# 02-M2_GoldFingers.net
KiCad netlist of a schematic drawn in Altium Designer
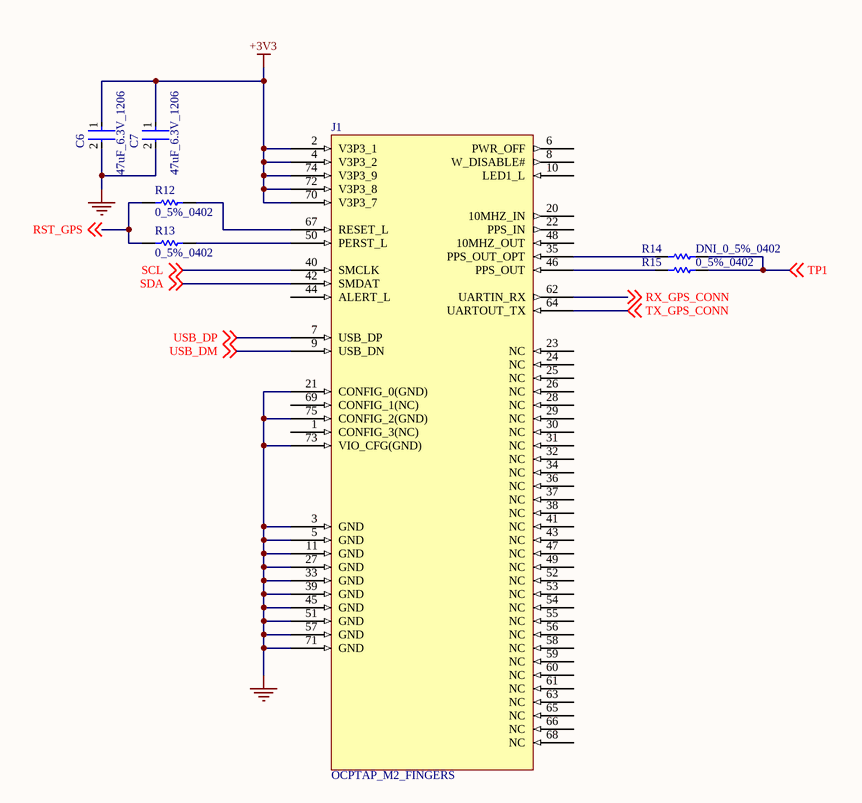
[diagram p0: 02-M2_GoldFingers.SchDoc]

(export (version "E")
  (design (tool "Eeschema 10.0.6"))
  (components
    (comp (ref "C6")
      (value "47uF_6.3V_1206")
      (footprint "FP-GRM31C-0_2-e0_3_0_8-IPC_C")
      (description "Chip Multilayer Ceramic Capacitors for General Purpose, 1206, 47uF, X5R, 15%, 20%, 6.3V")
      (fields (field (name "TOLERANCE") "20%") (field (name "VOLTAGE") "6.3V"))
      (libsource (lib "Altium Content Vault") (part "02cd4be3c70576c341d710602a673aa"))
    )
    (comp (ref "C7")
      (value "47uF_6.3V_1206")
      (footprint "FP-GRM31C-0_2-e0_3_0_8-IPC_C")
      (description "Chip Multilayer Ceramic Capacitors for General Purpose, 1206, 47uF, X5R, 15%, 20%, 6.3V")
      (fields (field (name "TOLERANCE") "20%") (field (name "VOLTAGE") "6.3V"))
      (libsource (lib "Altium Content Vault") (part "02cd4be3c70576c341d710602a673aa"))
    )
    (comp (ref "J1")
      (value "OCPTAP_M2_FINGERS")
      (footprint "OCPTAP M2 FINGERS")
      (libsource (lib "M2_Library") (part "OCPTAP_M2_FINGERS"))
    )
    (comp (ref "R12")
      (value "0_5%_0402")
      (footprint "RESC1005X40X25NL05T10")
      (fields (field (name "MANUFACTURER") "Panasonic") (field (name "PART NUMBER") "ERJ-U020R00X"))
      (libsource (lib "Altium Content Vault") (part "RES"))
    )
    (comp (ref "R13")
      (value "0_5%_0402")
      (footprint "RESC1005X40X25NL05T10")
      (fields (field (name "MANUFACTURER") "Panasonic") (field (name "PART NUMBER") "ERJ-U020R00X"))
      (libsource (lib "Altium Content Vault") (part "RES"))
    )
    (comp (ref "R14")
      (value "DNI_0_5%_0402")
      (footprint "RESC1005X40X25NL05T10")
      (fields (field (name "MANUFACTURER") "Panasonic") (field (name "PART NUMBER") "ERJ-U020R00X"))
      (libsource (lib "Altium Content Vault") (part "RES"))
    )
    (comp (ref "R15")
      (value "0_5%_0402")
      (footprint "RESC1005X40X25NL05T10")
      (fields (field (name "MANUFACTURER") "Panasonic") (field (name "PART NUMBER") "ERJ-U020R00X"))
      (libsource (lib "Altium Content Vault") (part "RES"))
    )
  )
  (nets
    (net (code "1") (name "+3V3") (class "Default")
      (node (ref "C6") (pin "1") (pinfunction "1_1") (pintype "passive"))
      (node (ref "C7") (pin "1") (pinfunction "1_1") (pintype "passive"))
      (node (ref "J1") (pin "2") (pinfunction "V3P3_1_2") (pintype "input"))
      (node (ref "J1") (pin "4") (pinfunction "V3P3_2_4") (pintype "input"))
      (node (ref "J1") (pin "70") (pinfunction "V3P3_7_70") (pintype "input"))
      (node (ref "J1") (pin "72") (pinfunction "V3P3_8_72") (pintype "input"))
      (node (ref "J1") (pin "74") (pinfunction "V3P3_9_74") (pintype "input"))
    )
    (net (code "2") (name "GND") (class "Default")
      (node (ref "C6") (pin "2") (pinfunction "2_2") (pintype "passive"))
      (node (ref "C7") (pin "2") (pinfunction "2_2") (pintype "passive"))
      (node (ref "J1") (pin "11") (pinfunction "GND_11") (pintype "input"))
      (node (ref "J1") (pin "21") (pinfunction "CONFIG_0(GND)_21") (pintype "input"))
      (node (ref "J1") (pin "27") (pinfunction "GND_27") (pintype "input"))
      (node (ref "J1") (pin "3") (pinfunction "GND_3") (pintype "input"))
      (node (ref "J1") (pin "33") (pinfunction "GND_33") (pintype "input"))
      (node (ref "J1") (pin "39") (pinfunction "GND_39") (pintype "input"))
      (node (ref "J1") (pin "45") (pinfunction "GND_45") (pintype "input"))
      (node (ref "J1") (pin "5") (pinfunction "GND_5") (pintype "input"))
      (node (ref "J1") (pin "51") (pinfunction "GND_51") (pintype "input"))
      (node (ref "J1") (pin "57") (pinfunction "GND_57") (pintype "input"))
      (node (ref "J1") (pin "71") (pinfunction "GND_71") (pintype "input"))
      (node (ref "J1") (pin "73") (pinfunction "VIO_CFG(GND)_73") (pintype "input"))
      (node (ref "J1") (pin "75") (pinfunction "CONFIG_2(GND)_75") (pintype "input"))
    )
    (net (code "3") (name "Net-(J1-PERST_L)") (class "Default")
      (node (ref "J1") (pin "50") (pinfunction "PERST_L_50") (pintype "input"))
      (node (ref "R13") (pin "2") (pinfunction "2_2") (pintype "passive"))
    )
    (net (code "4") (name "Net-(J1-PPS_OUT)") (class "Default")
      (node (ref "J1") (pin "46") (pinfunction "PPS_OUT_46") (pintype "input"))
      (node (ref "R15") (pin "1") (pinfunction "1_1") (pintype "passive"))
    )
    (net (code "5") (name "Net-(J1-PPS_OUT_OPT)") (class "Default")
      (node (ref "J1") (pin "35") (pinfunction "PPS_OUT_OPT_35") (pintype "input"))
      (node (ref "R14") (pin "1") (pinfunction "1_1") (pintype "passive"))
    )
    (net (code "6") (name "Net-(J1-RESET_L)") (class "Default")
      (node (ref "J1") (pin "67") (pinfunction "RESET_L_67") (pintype "input"))
      (node (ref "R12") (pin "2") (pinfunction "2_2") (pintype "passive"))
    )
    (net (code "7") (name "RST_GPS") (class "Default")
      (node (ref "R12") (pin "1") (pinfunction "1_1") (pintype "passive"))
      (node (ref "R13") (pin "1") (pinfunction "1_1") (pintype "passive"))
    )
    (net (code "8") (name "RX_GPS_CONN") (class "Default")
      (node (ref "J1") (pin "62") (pinfunction "UARTIN_RX_62") (pintype "output"))
    )
    (net (code "9") (name "SCL") (class "Default")
      (node (ref "J1") (pin "40") (pinfunction "SMCLK_40") (pintype "input"))
    )
    (net (code "10") (name "SDA") (class "Default")
      (node (ref "J1") (pin "42") (pinfunction "SMDAT_42") (pintype "input"))
    )
    (net (code "11") (name "TP1") (class "Default")
      (node (ref "R14") (pin "2") (pinfunction "2_2") (pintype "passive"))
      (node (ref "R15") (pin "2") (pinfunction "2_2") (pintype "passive"))
    )
    (net (code "12") (name "TX_GPS_CONN") (class "Default")
      (node (ref "J1") (pin "64") (pinfunction "UARTOUT_TX_64") (pintype "input"))
    )
    (net (code "13") (name "USB_DM") (class "Default")
      (node (ref "J1") (pin "9") (pinfunction "USB_DN_9") (pintype "input"))
    )
    (net (code "14") (name "USB_DP") (class "Default")
      (node (ref "J1") (pin "7") (pinfunction "USB_DP_7") (pintype "input"))
    )
    (net (code "15") (name "unconnected-(J1-10MHZ_IN-Pad20)") (class "Default")
      (node (ref "J1") (pin "20") (pinfunction "10MHZ_IN_20") (pintype "output"))
    )
    (net (code "16") (name "unconnected-(J1-10MHZ_OUT-Pad48)") (class "Default")
      (node (ref "J1") (pin "48") (pinfunction "10MHZ_OUT_48") (pintype "input"))
    )
    (net (code "17") (name "unconnected-(J1-ALERT_L-Pad44)") (class "Default")
      (node (ref "J1") (pin "44") (pinfunction "ALERT_L_44") (pintype "input"))
    )
    (net (code "18") (name "unconnected-(J1-CONFIG_1(NC)-Pad69)") (class "Default")
      (node (ref "J1") (pin "69") (pinfunction "CONFIG_1(NC)_69") (pintype "input"))
    )
    (net (code "19") (name "unconnected-(J1-CONFIG_3(NC)-Pad1)") (class "Default")
      (node (ref "J1") (pin "1") (pinfunction "CONFIG_3(NC)_1") (pintype "input"))
    )
    (net (code "20") (name "unconnected-(J1-LED1_L-Pad10)") (class "Default")
      (node (ref "J1") (pin "10") (pinfunction "LED1_L_10") (pintype "input"))
    )
    (net (code "21") (name "unconnected-(J1-NC-Pad23)") (class "Default")
      (node (ref "J1") (pin "23") (pinfunction "NC_23") (pintype "input"))
    )
    (net (code "22") (name "unconnected-(J1-NC-Pad24)") (class "Default")
      (node (ref "J1") (pin "24") (pinfunction "NC_24") (pintype "input"))
    )
    (net (code "23") (name "unconnected-(J1-NC-Pad25)") (class "Default")
      (node (ref "J1") (pin "25") (pinfunction "NC_25") (pintype "input"))
    )
    (net (code "24") (name "unconnected-(J1-NC-Pad26)") (class "Default")
      (node (ref "J1") (pin "26") (pinfunction "NC_26") (pintype "input"))
    )
    (net (code "25") (name "unconnected-(J1-NC-Pad28)") (class "Default")
      (node (ref "J1") (pin "28") (pinfunction "NC_28") (pintype "input"))
    )
    (net (code "26") (name "unconnected-(J1-NC-Pad29)") (class "Default")
      (node (ref "J1") (pin "29") (pinfunction "NC_29") (pintype "input"))
    )
    (net (code "27") (name "unconnected-(J1-NC-Pad30)") (class "Default")
      (node (ref "J1") (pin "30") (pinfunction "NC_30") (pintype "input"))
    )
    (net (code "28") (name "unconnected-(J1-NC-Pad31)") (class "Default")
      (node (ref "J1") (pin "31") (pinfunction "NC_31") (pintype "input"))
    )
    (net (code "29") (name "unconnected-(J1-NC-Pad32)") (class "Default")
      (node (ref "J1") (pin "32") (pinfunction "NC_32") (pintype "input"))
    )
    (net (code "30") (name "unconnected-(J1-NC-Pad34)") (class "Default")
      (node (ref "J1") (pin "34") (pinfunction "NC_34") (pintype "input"))
    )
    (net (code "31") (name "unconnected-(J1-NC-Pad36)") (class "Default")
      (node (ref "J1") (pin "36") (pinfunction "NC_36") (pintype "input"))
    )
    (net (code "32") (name "unconnected-(J1-NC-Pad37)") (class "Default")
      (node (ref "J1") (pin "37") (pinfunction "NC_37") (pintype "input"))
    )
    (net (code "33") (name "unconnected-(J1-NC-Pad38)") (class "Default")
      (node (ref "J1") (pin "38") (pinfunction "NC_38") (pintype "input"))
    )
    (net (code "34") (name "unconnected-(J1-NC-Pad41)") (class "Default")
      (node (ref "J1") (pin "41") (pinfunction "NC_41") (pintype "input"))
    )
    (net (code "35") (name "unconnected-(J1-NC-Pad43)") (class "Default")
      (node (ref "J1") (pin "43") (pinfunction "NC_43") (pintype "input"))
    )
    (net (code "36") (name "unconnected-(J1-NC-Pad47)") (class "Default")
      (node (ref "J1") (pin "47") (pinfunction "NC_47") (pintype "input"))
    )
    (net (code "37") (name "unconnected-(J1-NC-Pad49)") (class "Default")
      (node (ref "J1") (pin "49") (pinfunction "NC_49") (pintype "input"))
    )
    (net (code "38") (name "unconnected-(J1-NC-Pad52)") (class "Default")
      (node (ref "J1") (pin "52") (pinfunction "NC_52") (pintype "input"))
    )
    (net (code "39") (name "unconnected-(J1-NC-Pad53)") (class "Default")
      (node (ref "J1") (pin "53") (pinfunction "NC_53") (pintype "input"))
    )
    (net (code "40") (name "unconnected-(J1-NC-Pad54)") (class "Default")
      (node (ref "J1") (pin "54") (pinfunction "NC_54") (pintype "input"))
    )
    (net (code "41") (name "unconnected-(J1-NC-Pad55)") (class "Default")
      (node (ref "J1") (pin "55") (pinfunction "NC_55") (pintype "input"))
    )
    (net (code "42") (name "unconnected-(J1-NC-Pad56)") (class "Default")
      (node (ref "J1") (pin "56") (pinfunction "NC_56") (pintype "input"))
    )
    (net (code "43") (name "unconnected-(J1-NC-Pad58)") (class "Default")
      (node (ref "J1") (pin "58") (pinfunction "NC_58") (pintype "input"))
    )
    (net (code "44") (name "unconnected-(J1-NC-Pad59)") (class "Default")
      (node (ref "J1") (pin "59") (pinfunction "NC_59") (pintype "input"))
    )
    (net (code "45") (name "unconnected-(J1-NC-Pad60)") (class "Default")
      (node (ref "J1") (pin "60") (pinfunction "NC_60") (pintype "input"))
    )
    (net (code "46") (name "unconnected-(J1-NC-Pad61)") (class "Default")
      (node (ref "J1") (pin "61") (pinfunction "NC_61") (pintype "input"))
    )
    (net (code "47") (name "unconnected-(J1-NC-Pad63)") (class "Default")
      (node (ref "J1") (pin "63") (pinfunction "NC_63") (pintype "input"))
    )
    (net (code "48") (name "unconnected-(J1-NC-Pad65)") (class "Default")
      (node (ref "J1") (pin "65") (pinfunction "NC_65") (pintype "input"))
    )
    (net (code "49") (name "unconnected-(J1-NC-Pad66)") (class "Default")
      (node (ref "J1") (pin "66") (pinfunction "NC_66") (pintype "input"))
    )
    (net (code "50") (name "unconnected-(J1-NC-Pad68)") (class "Default")
      (node (ref "J1") (pin "68") (pinfunction "NC_68") (pintype "input"))
    )
    (net (code "51") (name "unconnected-(J1-PPS_IN-Pad22)") (class "Default")
      (node (ref "J1") (pin "22") (pinfunction "PPS_IN_22") (pintype "output"))
    )
    (net (code "52") (name "unconnected-(J1-PWR_OFF-Pad6)") (class "Default")
      (node (ref "J1") (pin "6") (pinfunction "PWR_OFF_6") (pintype "output"))
    )
    (net (code "53") (name "unconnected-(J1-W_DISABLE#-Pad8)") (class "Default")
      (node (ref "J1") (pin "8") (pinfunction "W_DISABLE#_8") (pintype "output"))
    )
  )
)
